# MCU.net
KiCad netlist of a schematic drawn in Altium Designer
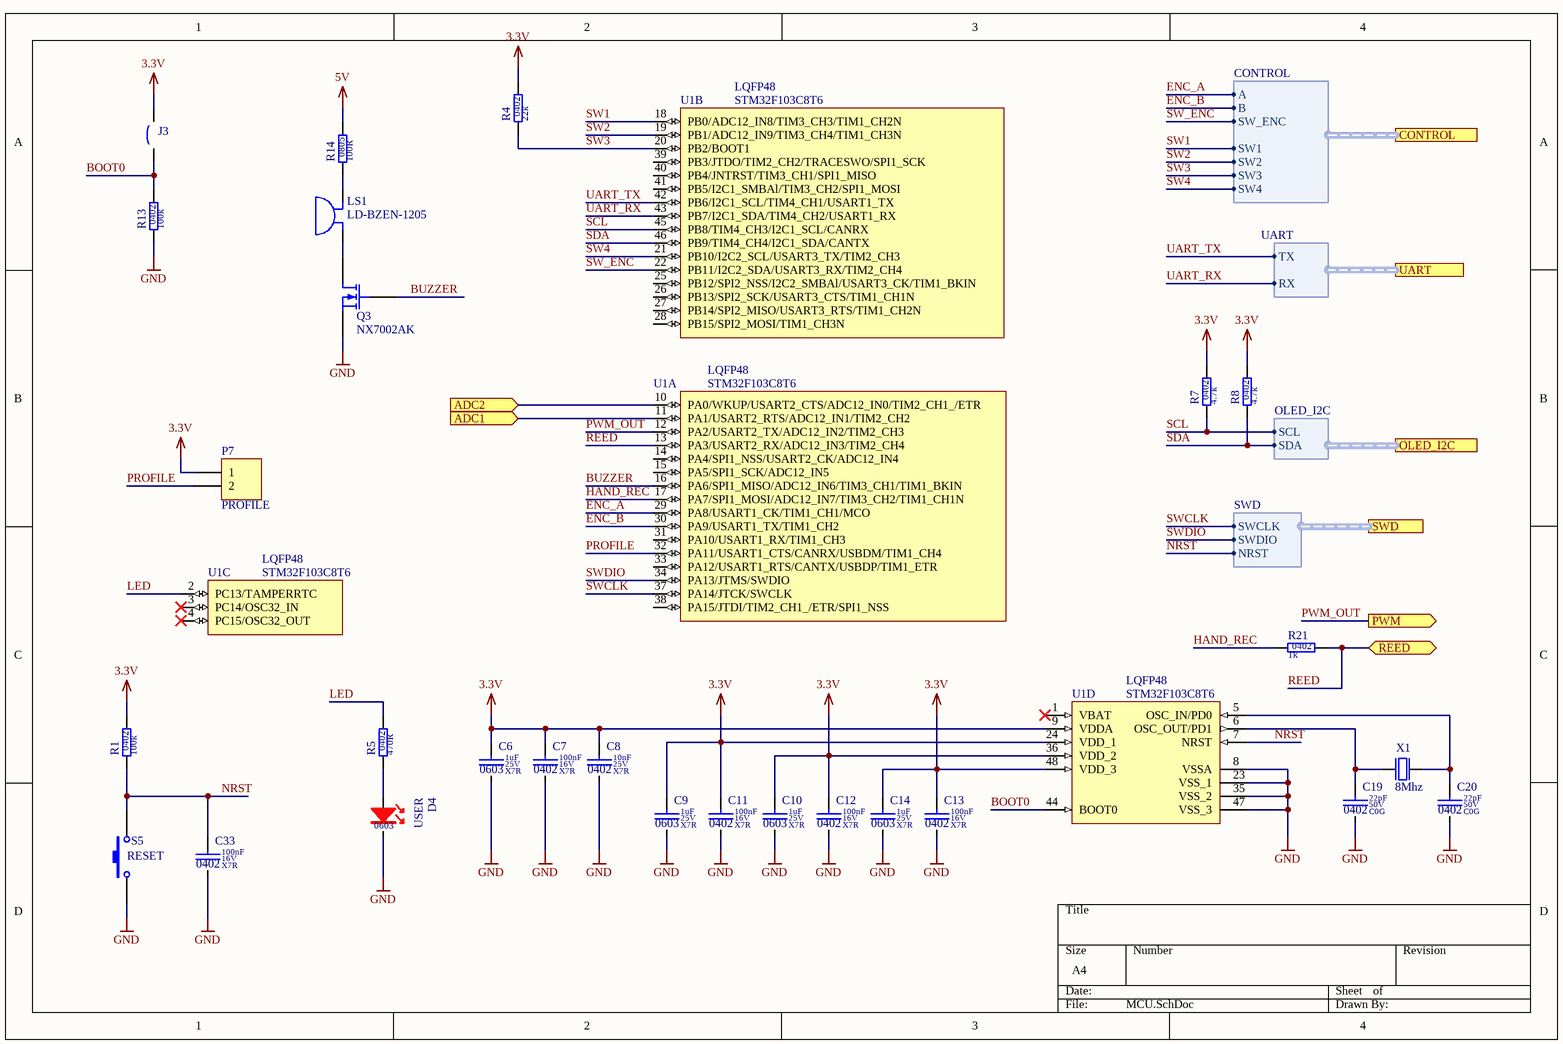
[diagram p0: MCU.SchDoc]

(export (version "E")
  (design (tool "Eeschema 10.0.6"))
  (components
    (comp (ref "C6")
      (value "1uF")
      (footprint "C_0603_1608")
      (description "Capacitor")
      (fields
        (field (name "DIELECTRIC") "X7R")
        (field (name "VOLTAGE") "25V")
        (field (name "SCH_FOOTPRINT") "0603")
        (field (name "PART NUMBER") "C_1uF_25V_X7R_0603_10")
        (field (name "MANUFACTURER") "Samsung")
      )
      (libsource (lib "Library") (part "C"))
    )
    (comp (ref "C7")
      (value "100nF")
      (footprint "C_0402_1005")
      (description "Capacitor")
      (fields
        (field (name "DIELECTRIC") "X7R")
        (field (name "VOLTAGE") "16V")
        (field (name "SCH_FOOTPRINT") "0402")
        (field (name "PART NUMBER") "C_100nF_16V_X7R_0402_10")
        (field (name "MANUFACTURER") "Murata")
      )
      (libsource (lib "Library") (part "C"))
    )
    (comp (ref "C8")
      (value "10nF")
      (footprint "C_0402_1005")
      (description "Capacitor")
      (fields
        (field (name "DIELECTRIC") "X7R")
        (field (name "VOLTAGE") "25V")
        (field (name "SCH_FOOTPRINT") "0402")
        (field (name "PART NUMBER") "C_10nF_25V_X7R_0402_10")
        (field (name "MANUFACTURER") "Murata")
      )
      (libsource (lib "Library") (part "C"))
    )
    (comp (ref "C9")
      (value "1uF")
      (footprint "C_0603_1608")
      (description "Capacitor")
      (fields
        (field (name "DIELECTRIC") "X7R")
        (field (name "VOLTAGE") "25V")
        (field (name "SCH_FOOTPRINT") "0603")
        (field (name "PART NUMBER") "C_1uF_25V_X7R_0603_10")
        (field (name "MANUFACTURER") "Samsung")
      )
      (libsource (lib "Library") (part "C"))
    )
    (comp (ref "C10")
      (value "1uF")
      (footprint "C_0603_1608")
      (description "Capacitor")
      (fields
        (field (name "DIELECTRIC") "X7R")
        (field (name "VOLTAGE") "25V")
        (field (name "SCH_FOOTPRINT") "0603")
        (field (name "PART NUMBER") "C_1uF_25V_X7R_0603_10")
        (field (name "MANUFACTURER") "Samsung")
      )
      (libsource (lib "Library") (part "C"))
    )
    (comp (ref "C11")
      (value "100nF")
      (footprint "C_0402_1005")
      (description "Capacitor")
      (fields
        (field (name "DIELECTRIC") "X7R")
        (field (name "VOLTAGE") "16V")
        (field (name "SCH_FOOTPRINT") "0402")
        (field (name "PART NUMBER") "C_100nF_16V_X7R_0402_10")
        (field (name "MANUFACTURER") "Murata")
      )
      (libsource (lib "Library") (part "C"))
    )
    (comp (ref "C12")
      (value "100nF")
      (footprint "C_0402_1005")
      (description "Capacitor")
      (fields
        (field (name "DIELECTRIC") "X7R")
        (field (name "VOLTAGE") "16V")
        (field (name "SCH_FOOTPRINT") "0402")
        (field (name "PART NUMBER") "C_100nF_16V_X7R_0402_10")
        (field (name "MANUFACTURER") "Murata")
      )
      (libsource (lib "Library") (part "C"))
    )
    (comp (ref "C13")
      (value "100nF")
      (footprint "C_0402_1005")
      (description "Capacitor")
      (fields
        (field (name "DIELECTRIC") "X7R")
        (field (name "VOLTAGE") "16V")
        (field (name "SCH_FOOTPRINT") "0402")
        (field (name "PART NUMBER") "C_100nF_16V_X7R_0402_10")
        (field (name "MANUFACTURER") "Murata")
      )
      (libsource (lib "Library") (part "C"))
    )
    (comp (ref "C14")
      (value "1uF")
      (footprint "C_0603_1608")
      (description "Capacitor")
      (fields
        (field (name "DIELECTRIC") "X7R")
        (field (name "VOLTAGE") "25V")
        (field (name "SCH_FOOTPRINT") "0603")
        (field (name "PART NUMBER") "C_1uF_25V_X7R_0603_10")
        (field (name "MANUFACTURER") "Samsung")
      )
      (libsource (lib "Library") (part "C"))
    )
    (comp (ref "C19")
      (value "22pF")
      (footprint "C_0402_1005")
      (description "Capacitor")
      (fields
        (field (name "DIELECTRIC") "C0G")
        (field (name "VOLTAGE") "50V")
        (field (name "SCH_FOOTPRINT") "0402")
        (field (name "PART NUMBER") "C_22pF_50V_C0G_0402_5")
        (field (name "MANUFACTURER") "AVX")
      )
      (libsource (lib "Library") (part "C"))
    )
    (comp (ref "C20")
      (value "22pF")
      (footprint "C_0402_1005")
      (description "Capacitor")
      (fields
        (field (name "DIELECTRIC") "C0G")
        (field (name "VOLTAGE") "50V")
        (field (name "SCH_FOOTPRINT") "0402")
        (field (name "PART NUMBER") "C_22pF_50V_C0G_0402_5")
        (field (name "MANUFACTURER") "AVX")
      )
      (libsource (lib "Library") (part "C"))
    )
    (comp (ref "C33")
      (value "100nF")
      (footprint "C_0402_1005")
      (description "Capacitor")
      (fields
        (field (name "DIELECTRIC") "X7R")
        (field (name "VOLTAGE") "16V")
        (field (name "SCH_FOOTPRINT") "0402")
        (field (name "PART NUMBER") "C_100nF_16V_X7R_0402_10")
        (field (name "MANUFACTURER") "Murata")
      )
      (libsource (lib "Library") (part "C"))
    )
    (comp (ref "D4")
      (value "USER")
      (footprint "OL_0603_1608")
      (description "LED_RED")
      (fields
        (field (name "SCH_FOOTPRINT") "0603")
        (field (name "PART NUMBER") "OL_R_0603")
        (field (name "MANUFACTURER") "Lite-On")
      )
      (libsource (lib "Library") (part "OL_R"))
    )
    (comp (ref "J3")
      (value "BOOT0")
      (footprint "Contact_Point_2_Pad")
      (description "Contact_Point_2_Pad")
      (libsource (lib "soldering_station") (part "Contact_Point_2_Pad"))
    )
    (comp (ref "LS1")
      (value "LD-BZEN-1205")
      (footprint "LD-BZEN-1205")
      (description "Przetwornik dźwięku: elektromagnetyczny; THT; 2,4kHz; 40mA; H: 9mm")
      (libsource (lib "soldering_station") (part "LD-BZEN-1205"))
    )
    (comp (ref "P7")
      (value "PROFILE")
      (footprint "P_HEADER_1x2_2.54")
      (description "Header, 2-Pin")
      (fields (field (name "PART NUMBER") "P_HEADER_1x2_2.54") (field (name "MANUFACTURER") "Connfly"))
      (libsource (lib "Library") (part "P_HEADER_1x2"))
    )
    (comp (ref "Q3")
      (value "NX7002AK")
      (footprint "NX7002AK.215")
      (description "Tranzystor: N-MOSFET; unipolarny; 60V; 0,12A; 325mW; SOT23")
      (libsource (lib "soldering_station") (part "NX7002AK.215"))
    )
    (comp (ref "R1")
      (value "100k")
      (footprint "R_0402_1005")
      (fields
        (field (name "SCH_FOOTPRINT") "0402")
        (field (name "PART NUMBER") "R_100k_0402_1")
        (field (name "VOLTAGE") "50V")
        (field (name "POWER") "63mW")
      )
      (libsource (lib "Library") (part "R"))
    )
    (comp (ref "R4")
      (value "22k")
      (footprint "R_0402_1005")
      (fields
        (field (name "SCH_FOOTPRINT") "0402")
        (field (name "PART NUMBER") "R_22k_0402_1")
        (field (name "VOLTAGE") "50V")
        (field (name "POWER") "63mW")
      )
      (libsource (lib "Library") (part "R"))
    )
    (comp (ref "R5")
      (value "470R")
      (footprint "R_0402_1005")
      (fields
        (field (name "SCH_FOOTPRINT") "0402")
        (field (name "PART NUMBER") "R_470R_0402_1")
        (field (name "VOLTAGE") "50V")
        (field (name "POWER") "63mW")
      )
      (libsource (lib "Library") (part "R"))
    )
    (comp (ref "R7")
      (value "4.7k")
      (footprint "R_0402_1005")
      (fields
        (field (name "SCH_FOOTPRINT") "0402")
        (field (name "PART NUMBER") "R_100k_0402_1")
        (field (name "VOLTAGE") "50V")
        (field (name "POWER") "63mW")
      )
      (libsource (lib "Library") (part "R"))
    )
    (comp (ref "R8")
      (value "4.7k")
      (footprint "R_0402_1005")
      (fields
        (field (name "SCH_FOOTPRINT") "0402")
        (field (name "PART NUMBER") "R_100k_0402_1")
        (field (name "VOLTAGE") "50V")
        (field (name "POWER") "63mW")
      )
      (libsource (lib "Library") (part "R"))
    )
    (comp (ref "R13")
      (value "100k")
      (footprint "R_0402_1005")
      (fields
        (field (name "SCH_FOOTPRINT") "0402")
        (field (name "PART NUMBER") "R_100k_0402_1")
        (field (name "VOLTAGE") "50V")
        (field (name "POWER") "63mW")
      )
      (libsource (lib "Library") (part "R"))
    )
    (comp (ref "R14")
      (value "100R")
      (footprint "R_0805_2012")
      (fields
        (field (name "SCH_FOOTPRINT") "0805")
        (field (name "PART NUMBER") "R_100R_0805_1")
        (field (name "VOLTAGE") "150V")
        (field (name "POWER") "125mW")
      )
      (libsource (lib "Library") (part "R"))
    )
    (comp (ref "R21")
      (value "1k")
      (footprint "R_0402_1005")
      (fields
        (field (name "SCH_FOOTPRINT") "0402")
        (field (name "PART NUMBER") "R_1k_0402_1")
        (field (name "VOLTAGE") "50V")
        (field (name "POWER") "63mW")
      )
      (libsource (lib "Library") (part "R"))
    )
    (comp (ref "S5")
      (value "RESET")
      (footprint "S_TACTSWITCH3x6")
      (description "Tact Switch")
      (fields (field (name "PART NUMBER") "S_TACTSWITCH") (field (name "MANUFACTURER") "Ninigi"))
      (libsource (lib "Library") (part "S_TACTSWITCH"))
    )
    (comp (ref "U1")
      (value "STM32F103C8T6")
      (footprint "LQFP48_7x7")
      (fields
        (field (name "SCH_FOOTPRINT") "LQFP48")
        (field (name "PART NUMBER") "UP_STM32F103C8T6")
        (field (name "MANUFACTURER") "STMicroelectronics")
      )
      (libsource (lib "Library") (part "UP_STM32F103Cx"))
    )
    (comp (ref "X1")
      (value "8Mhz")
      (footprint "X_HC49_THT")
      (description "Resonator Ceramic")
      (fields
        (field (name "PART NUMBER") "X_HC49US-FF5F18-16.0000")
        (field (name "MANUFACTURER PART NUMBER") "HC49US-FF3F18-16.0000")
      )
      (libsource (lib "Library") (part "X_GENERIC"))
    )
  )
  (nets
    (net (code "5") (name "/ADC1") (class "Default")
      (node (ref "U1") (pin "11") (pinfunction "PA1/USART2_RTS/ADC12_IN1/TIM2_CH2_11") (pintype "bidirectional"))
    )
    (net (code "6") (name "/ADC2") (class "Default")
      (node (ref "U1") (pin "10") (pinfunction "PA0/WKUP/USART2_CTS/ADC12_IN0/TIM2_CH1_/ETR_10") (pintype "bidirectional"))
    )
    (net (code "7") (name "/BOOT0") (class "Default")
      (node (ref "J3") (pin "1") (pinfunction "1_1") (pintype "passive"))
      (node (ref "R13") (pin "2") (pinfunction "2_2") (pintype "passive"))
      (node (ref "U1") (pin "44") (pinfunction "BOOT0_44") (pintype "input"))
    )
    (net (code "8") (name "/BUZZER") (class "Default")
      (node (ref "Q3") (pin "1") (pinfunction "G_1") (pintype "passive"))
      (node (ref "U1") (pin "16") (pinfunction "PA6/SPI1_MISO/ADC12_IN6/TIM3_CH1/TIM1_BKIN_16") (pintype "bidirectional"))
    )
    (net (code "9") (name "/ENC_A") (class "Default")
      (node (ref "U1") (pin "29") (pinfunction "PA8/USART1_CK/TIM1_CH1/MCO_29") (pintype "bidirectional"))
    )
    (net (code "10") (name "/ENC_B") (class "Default")
      (node (ref "U1") (pin "30") (pinfunction "PA9/USART1_TX/TIM1_CH2_30") (pintype "bidirectional"))
    )
    (net (code "11") (name "/HAND_REC") (class "Default")
      (node (ref "R21") (pin "1") (pinfunction "1_1") (pintype "passive"))
      (node (ref "U1") (pin "17") (pinfunction "PA7/SPI1_MOSI/ADC12_IN7/TIM3_CH2/TIM1_CH1N_17") (pintype "bidirectional"))
    )
    (net (code "12") (name "/LED") (class "Default")
      (node (ref "R5") (pin "2") (pinfunction "2_2") (pintype "passive"))
      (node (ref "U1") (pin "2") (pinfunction "PC13/TAMPERRTC_2") (pintype "bidirectional"))
    )
    (net (code "13") (name "/NRST") (class "Default")
      (node (ref "C33") (pin "1") (pinfunction "1_1") (pintype "passive"))
      (node (ref "R1") (pin "1") (pinfunction "1_1") (pintype "passive"))
      (node (ref "S5") (pin "2") (pinfunction "2_2") (pintype "passive"))
      (node (ref "U1") (pin "7") (pinfunction "NRST_7") (pintype "input"))
    )
    (net (code "14") (name "/PROFILE") (class "Default")
      (node (ref "P7") (pin "2") (pinfunction "2_2") (pintype "passive"))
      (node (ref "U1") (pin "32") (pinfunction "PA11/USART1_CTS/CANRX/USBDM/TIM1_CH4_32") (pintype "bidirectional"))
    )
    (net (code "15") (name "/PWM_OUT") (class "Default")
      (node (ref "U1") (pin "12") (pinfunction "PA2/USART2_TX/ADC12_IN2/TIM2_CH3_12") (pintype "bidirectional"))
    )
    (net (code "16") (name "/REED") (class "Default")
      (node (ref "R21") (pin "2") (pinfunction "2_2") (pintype "passive"))
      (node (ref "U1") (pin "13") (pinfunction "PA3/USART2_RX/ADC12_IN3/TIM2_CH4_13") (pintype "bidirectional"))
    )
    (net (code "17") (name "/SCL") (class "Default")
      (node (ref "R7") (pin "1") (pinfunction "1_1") (pintype "passive"))
      (node (ref "U1") (pin "45") (pinfunction "PB8/TIM4_CH3/I2C1_SCL/CANRX_45") (pintype "bidirectional"))
    )
    (net (code "18") (name "/SDA") (class "Default")
      (node (ref "R8") (pin "1") (pinfunction "1_1") (pintype "passive"))
      (node (ref "U1") (pin "46") (pinfunction "PB9/TIM4_CH4/I2C1_SDA/CANTX_46") (pintype "bidirectional"))
    )
    (net (code "19") (name "/SW1") (class "Default")
      (node (ref "U1") (pin "18") (pinfunction "PB0/ADC12_IN8/TIM3_CH3/TIM1_CH2N_18") (pintype "bidirectional"))
    )
    (net (code "20") (name "/SW2") (class "Default")
      (node (ref "U1") (pin "19") (pinfunction "PB1/ADC12_IN9/TIM3_CH4/TIM1_CH3N_19") (pintype "bidirectional"))
    )
    (net (code "21") (name "/SW3") (class "Default")
      (node (ref "R4") (pin "1") (pinfunction "1_1") (pintype "passive"))
      (node (ref "U1") (pin "20") (pinfunction "PB2/BOOT1_20") (pintype "bidirectional"))
    )
    (net (code "22") (name "/SW4") (class "Default")
      (node (ref "U1") (pin "21") (pinfunction "PB10/I2C2_SCL/USART3_TX/TIM2_CH3_21") (pintype "bidirectional"))
    )
    (net (code "23") (name "/SWCLK") (class "Default")
      (node (ref "U1") (pin "37") (pinfunction "PA14/JTCK/SWCLK_37") (pintype "bidirectional"))
    )
    (net (code "24") (name "/SWDIO") (class "Default")
      (node (ref "U1") (pin "34") (pinfunction "PA13/JTMS/SWDIO_34") (pintype "bidirectional"))
    )
    (net (code "25") (name "/SW_ENC") (class "Default")
      (node (ref "U1") (pin "22") (pinfunction "PB11/I2C2_SDA/USART3_RX/TIM2_CH4_22") (pintype "bidirectional"))
    )
    (net (code "26") (name "/UART_RX") (class "Default")
      (node (ref "U1") (pin "43") (pinfunction "PB7/I2C1_SDA/TIM4_CH2/USART1_RX_43") (pintype "bidirectional"))
    )
    (net (code "27") (name "/UART_TX") (class "Default")
      (node (ref "U1") (pin "42") (pinfunction "PB6/I2C1_SCL/TIM4_CH1/USART1_TX_42") (pintype "bidirectional"))
    )
    (net (code "32") (name "3.3V") (class "Default")
      (node (ref "C10") (pin "1") (pinfunction "1_1") (pintype "passive"))
      (node (ref "C11") (pin "1") (pinfunction "1_1") (pintype "passive"))
      (node (ref "C12") (pin "1") (pinfunction "1_1") (pintype "passive"))
      (node (ref "C13") (pin "1") (pinfunction "1_1") (pintype "passive"))
      (node (ref "C14") (pin "1") (pinfunction "1_1") (pintype "passive"))
      (node (ref "C6") (pin "1") (pinfunction "1_1") (pintype "passive"))
      (node (ref "C7") (pin "1") (pinfunction "1_1") (pintype "passive"))
      (node (ref "C8") (pin "1") (pinfunction "1_1") (pintype "passive"))
      (node (ref "C9") (pin "1") (pinfunction "1_1") (pintype "passive"))
      (node (ref "J3") (pin "2") (pinfunction "2_2") (pintype "passive"))
      (node (ref "P7") (pin "1") (pinfunction "1_1") (pintype "passive"))
      (node (ref "R1") (pin "2") (pinfunction "2_2") (pintype "passive"))
      (node (ref "R4") (pin "2") (pinfunction "2_2") (pintype "passive"))
      (node (ref "R7") (pin "2") (pinfunction "2_2") (pintype "passive"))
      (node (ref "R8") (pin "2") (pinfunction "2_2") (pintype "passive"))
      (node (ref "U1") (pin "24") (pinfunction "VDD_1_24") (pintype "input"))
      (node (ref "U1") (pin "36") (pinfunction "VDD_2_36") (pintype "input"))
      (node (ref "U1") (pin "48") (pinfunction "VDD_3_48") (pintype "input"))
      (node (ref "U1") (pin "9") (pinfunction "VDDA_9") (pintype "input"))
    )
    (net (code "33") (name "5V") (class "Default")
      (node (ref "R14") (pin "2") (pinfunction "2_2") (pintype "passive"))
    )
    (net (code "34") (name "GND") (class "Default")
      (node (ref "C10") (pin "2") (pinfunction "2_2") (pintype "passive"))
      (node (ref "C11") (pin "2") (pinfunction "2_2") (pintype "passive"))
      (node (ref "C12") (pin "2") (pinfunction "2_2") (pintype "passive"))
      (node (ref "C13") (pin "2") (pinfunction "2_2") (pintype "passive"))
      (node (ref "C14") (pin "2") (pinfunction "2_2") (pintype "passive"))
      (node (ref "C19") (pin "2") (pinfunction "2_2") (pintype "passive"))
      (node (ref "C20") (pin "2") (pinfunction "2_2") (pintype "passive"))
      (node (ref "C33") (pin "2") (pinfunction "2_2") (pintype "passive"))
      (node (ref "C6") (pin "2") (pinfunction "2_2") (pintype "passive"))
      (node (ref "C7") (pin "2") (pinfunction "2_2") (pintype "passive"))
      (node (ref "C8") (pin "2") (pinfunction "2_2") (pintype "passive"))
      (node (ref "C9") (pin "2") (pinfunction "2_2") (pintype "passive"))
      (node (ref "D4") (pin "1") (pinfunction "K_1") (pintype "passive"))
      (node (ref "Q3") (pin "2") (pinfunction "S_2") (pintype "passive"))
      (node (ref "R13") (pin "1") (pinfunction "1_1") (pintype "passive"))
      (node (ref "S5") (pin "1") (pinfunction "1_1") (pintype "passive"))
      (node (ref "U1") (pin "23") (pinfunction "VSS_1_23") (pintype "power_in"))
      (node (ref "U1") (pin "35") (pinfunction "VSS_2_35") (pintype "power_in"))
      (node (ref "U1") (pin "47") (pinfunction "VSS_3_47") (pintype "power_in"))
      (node (ref "U1") (pin "8") (pinfunction "VSSA_8") (pintype "power_in"))
    )
    (net (code "35") (name "Net-(D4-A)") (class "Default")
      (node (ref "D4") (pin "2") (pinfunction "A_2") (pintype "passive"))
      (node (ref "R5") (pin "1") (pinfunction "1_1") (pintype "passive"))
    )
    (net (code "36") (name "Net-(LS1-Pad1)") (class "Default")
      (node (ref "LS1") (pin "1") (pinfunction "1_1") (pintype "passive"))
      (node (ref "R14") (pin "1") (pinfunction "1_1") (pintype "passive"))
    )
    (net (code "37") (name "Net-(Q3-D)") (class "Default")
      (node (ref "LS1") (pin "2") (pinfunction "2_2") (pintype "passive"))
      (node (ref "Q3") (pin "3") (pinfunction "D_3") (pintype "passive"))
    )
    (net (code "38") (name "Net-(U1D-OSC_IN{slash}PD0)") (class "Default")
      (node (ref "C20") (pin "1") (pinfunction "1_1") (pintype "passive"))
      (node (ref "U1") (pin "5") (pinfunction "OSC_IN/PD0_5") (pintype "input"))
      (node (ref "X1") (pin "2") (pintype "passive"))
    )
    (net (code "39") (name "Net-(U1D-OSC_OUT{slash}PD1)") (class "Default")
      (node (ref "C19") (pin "1") (pinfunction "1_1") (pintype "passive"))
      (node (ref "U1") (pin "6") (pinfunction "OSC_OUT/PD1_6") (pintype "output"))
      (node (ref "X1") (pin "1") (pintype "passive"))
    )
    (net (code "40") (name "unconnected-(U1A-PA4{slash}SPI1_NSS{slash}USART2_CK{slash}ADC12_IN4-Pad14)") (class "Default")
      (node (ref "U1") (pin "14") (pinfunction "PA4/SPI1_NSS/USART2_CK/ADC12_IN4_14") (pintype "bidirectional"))
    )
    (net (code "41") (name "unconnected-(U1A-PA5{slash}SPI1_SCK{slash}ADC12_IN5-Pad15)") (class "Default")
      (node (ref "U1") (pin "15") (pinfunction "PA5/SPI1_SCK/ADC12_IN5_15") (pintype "bidirectional"))
    )
    (net (code "42") (name "unconnected-(U1A-PA10{slash}USART1_RX{slash}TIM1_CH3-Pad31)") (class "Default")
      (node (ref "U1") (pin "31") (pinfunction "PA10/USART1_RX/TIM1_CH3_31") (pintype "bidirectional"))
    )
    (net (code "43") (name "unconnected-(U1A-PA12{slash}USART1_RTS{slash}CANTX{slash}USBDP{slash}TIM1_ETR-Pad33)") (class "Default")
      (node (ref "U1") (pin "33") (pinfunction "PA12/USART1_RTS/CANTX/USBDP/TIM1_ETR_33") (pintype "bidirectional"))
    )
    (net (code "44") (name "unconnected-(U1A-PA15{slash}JTDI{slash}TIM2_CH1_{slash}ETR{slash}SPI1_NSS-Pad38)") (class "Default")
      (node (ref "U1") (pin "38") (pinfunction "PA15/JTDI/TIM2_CH1_/ETR/SPI1_NSS_38") (pintype "bidirectional"))
    )
    (net (code "45") (name "unconnected-(U1B-PB3{slash}JTDO{slash}TIM2_CH2{slash}TRACESWO{slash}SPI1_SCK-Pad39)") (class "Default")
      (node (ref "U1") (pin "39") (pinfunction "PB3/JTDO/TIM2_CH2/TRACESWO/SPI1_SCK_39") (pintype "bidirectional"))
    )
    (net (code "46") (name "unconnected-(U1B-PB4{slash}JNTRST{slash}TIM3_CH1{slash}SPI1_MISO-Pad40)") (class "Default")
      (node (ref "U1") (pin "40") (pinfunction "PB4/JNTRST/TIM3_CH1/SPI1_MISO_40") (pintype "bidirectional"))
    )
    (net (code "47") (name "unconnected-(U1B-PB5{slash}I2C1_SMBAl{slash}TIM3_CH2{slash}SPI1_MOSI-Pad41)") (class "Default")
      (node (ref "U1") (pin "41") (pinfunction "PB5/I2C1_SMBAl/TIM3_CH2/SPI1_MOSI_41") (pintype "bidirectional"))
    )
    (net (code "48") (name "unconnected-(U1B-PB12{slash}SPI2_NSS{slash}I2C2_SMBAl{slash}USART3_CK{slash}TIM1_BKIN-Pad25)") (class "Default")
      (node (ref "U1") (pin "25") (pinfunction "PB12/SPI2_NSS/I2C2_SMBAl/USART3_CK/TIM1_BKIN_25") (pintype "bidirectional"))
    )
    (net (code "49") (name "unconnected-(U1B-PB13{slash}SPI2_SCK{slash}USART3_CTS{slash}TIM1_CH1N-Pad26)") (class "Default")
      (node (ref "U1") (pin "26") (pinfunction "PB13/SPI2_SCK/USART3_CTS/TIM1_CH1N_26") (pintype "bidirectional"))
    )
    (net (code "50") (name "unconnected-(U1B-PB14{slash}SPI2_MISO{slash}USART3_RTS{slash}TIM1_CH2N-Pad27)") (class "Default")
      (node (ref "U1") (pin "27") (pinfunction "PB14/SPI2_MISO/USART3_RTS/TIM1_CH2N_27") (pintype "bidirectional"))
    )
    (net (code "51") (name "unconnected-(U1B-PB15{slash}SPI2_MOSI{slash}TIM1_CH3N-Pad28)") (class "Default")
      (node (ref "U1") (pin "28") (pinfunction "PB15/SPI2_MOSI/TIM1_CH3N_28") (pintype "bidirectional"))
    )
    (net (code "52") (name "unconnected-(U1C-PC14{slash}OSC32_IN-Pad3)") (class "Default")
      (node (ref "U1") (pin "3") (pinfunction "PC14/OSC32_IN_3") (pintype "bidirectional+no_connect"))
    )
    (net (code "53") (name "unconnected-(U1C-PC15{slash}OSC32_OUT-Pad4)") (class "Default")
      (node (ref "U1") (pin "4") (pinfunction "PC15/OSC32_OUT_4") (pintype "bidirectional+no_connect"))
    )
    (net (code "54") (name "unconnected-(U1D-VBAT-Pad1)") (class "Default")
      (node (ref "U1") (pin "1") (pinfunction "VBAT_1") (pintype "input+no_connect"))
    )
  )
)
